# ICM-45686.net
KiCad netlist of a schematic drawn in EasyEDA Pro
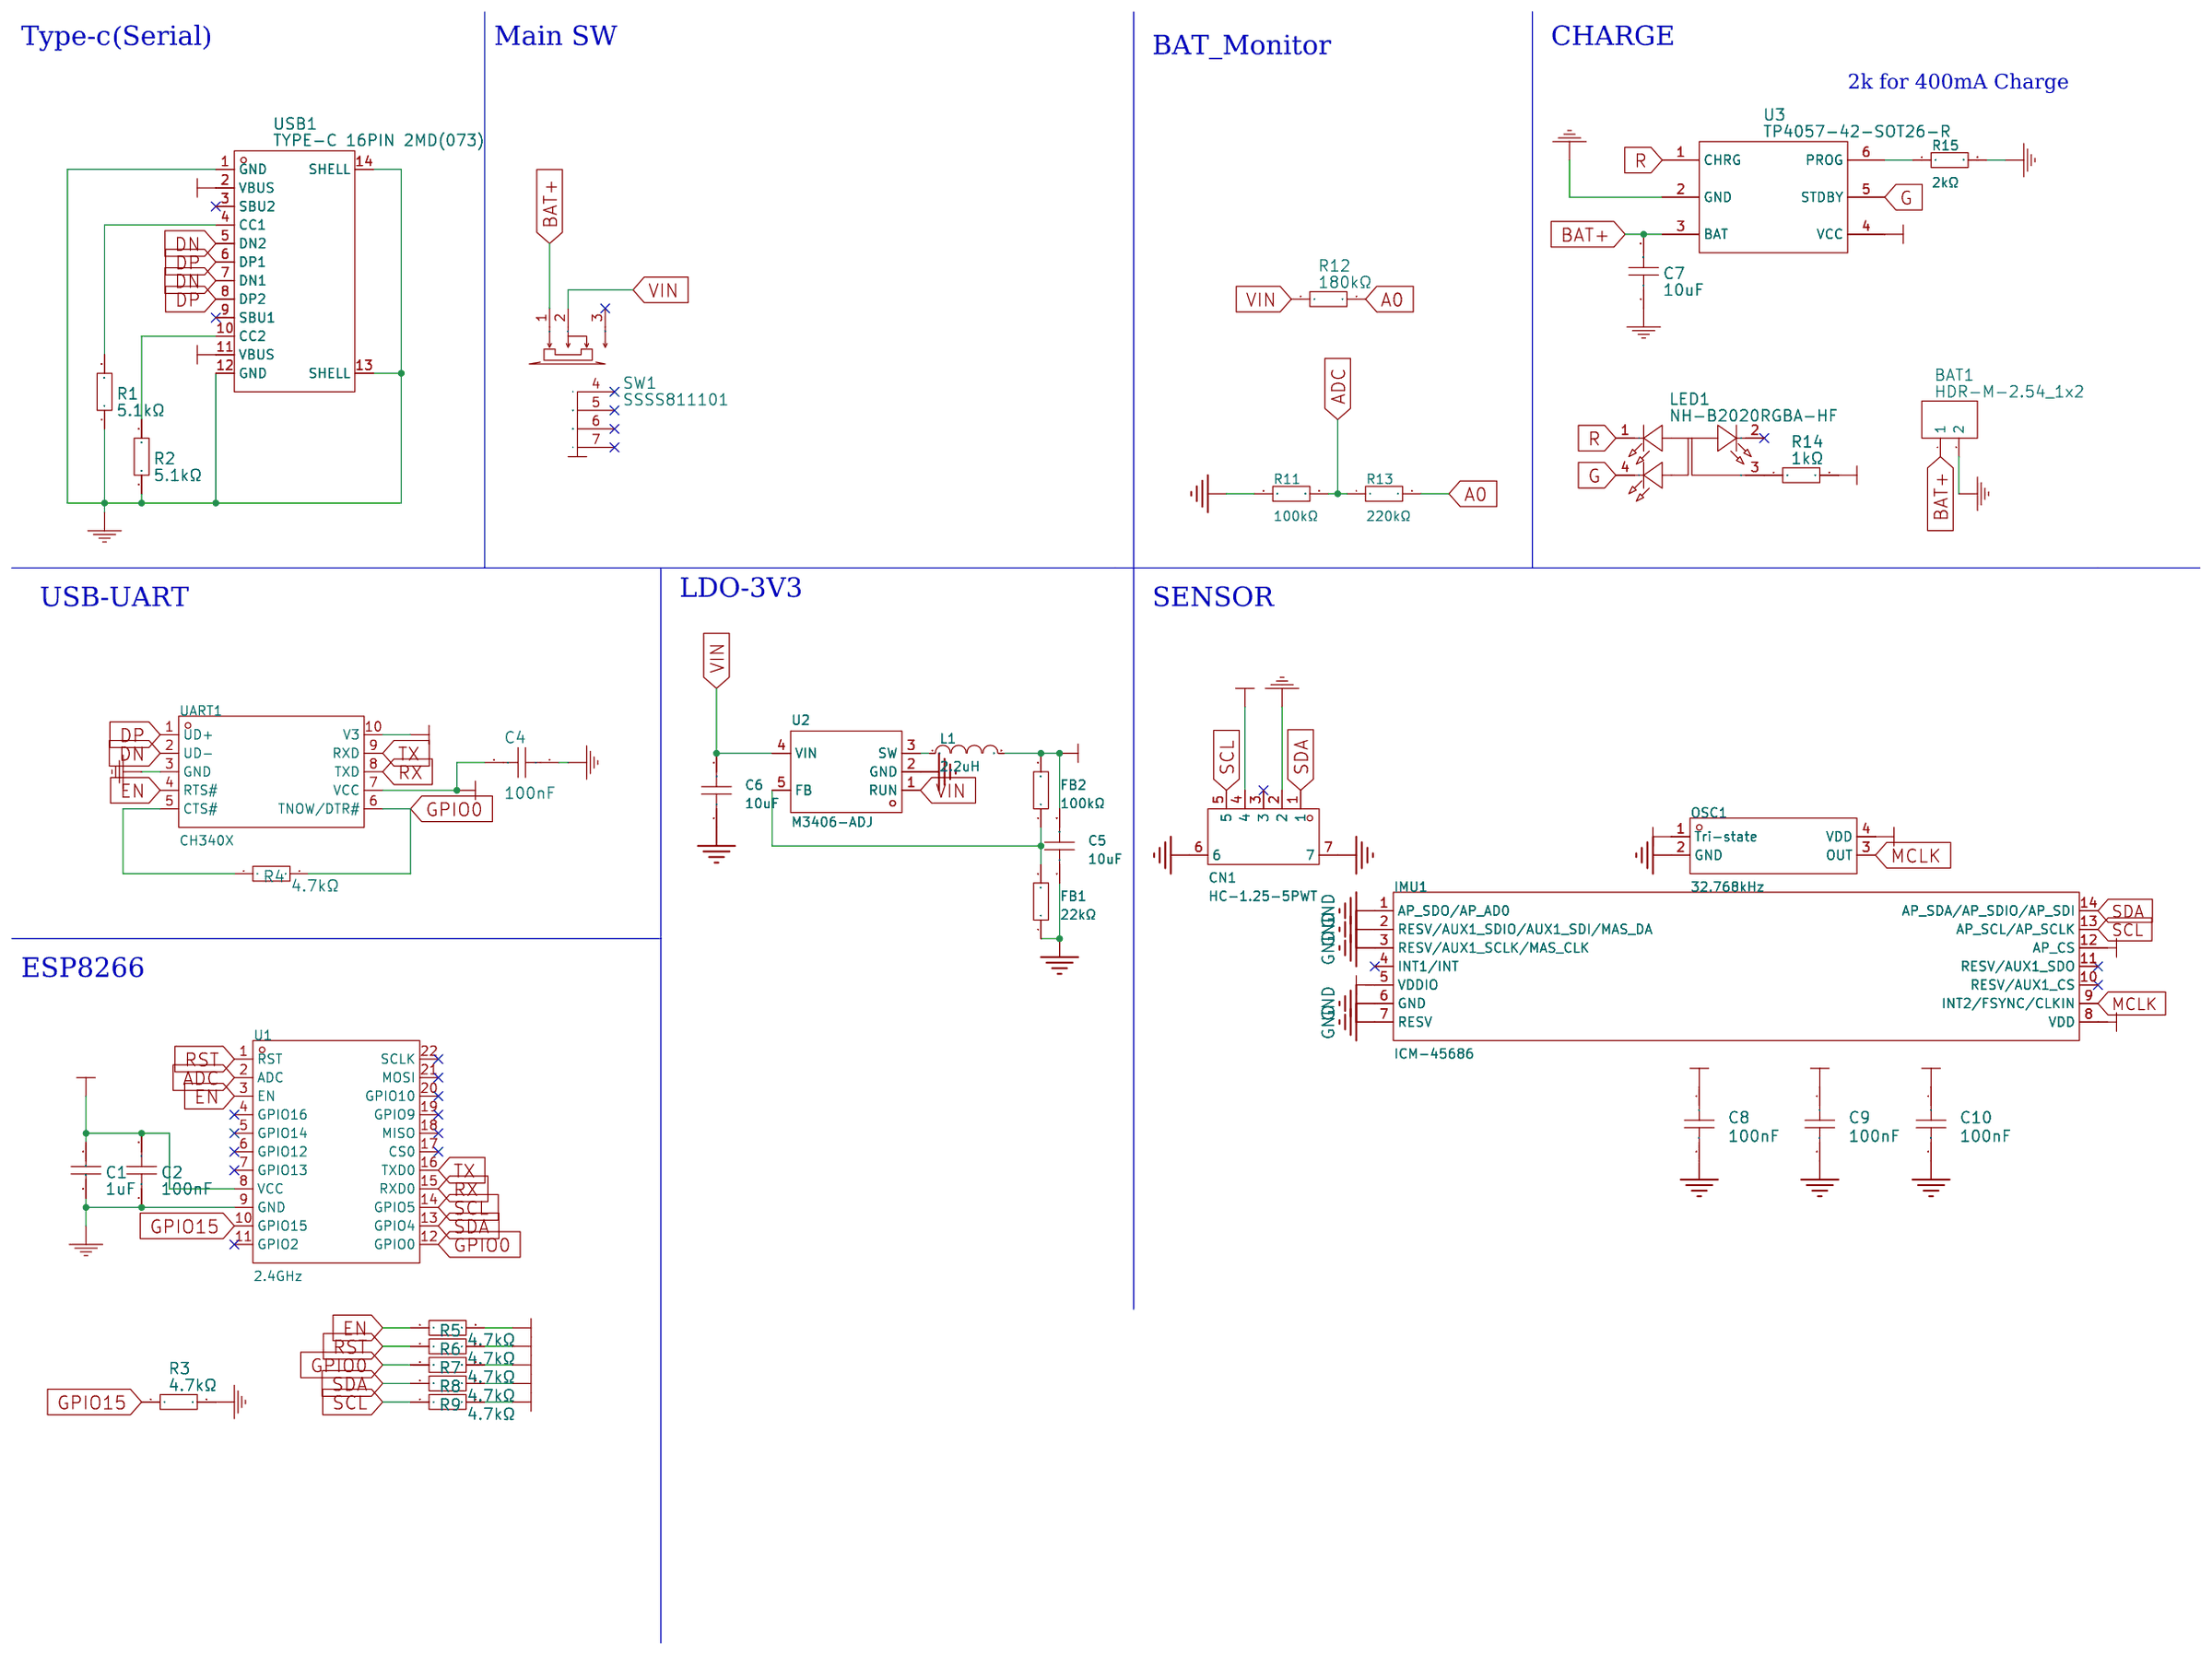
[diagram p0: schematic sheet]

(export (version "E")
  (design (tool "Eeschema 10.0.6"))
  (components
    (comp (ref "BAT1")
      (value "HDR-M-2.54_1x2")
      (footprint "easyedapro:HDR-M-2.54_1X2")
      (libsource (lib "easyedapro") (part "HDR-M-2.54_1x2"))
    )
    (comp (ref "C1")
      (value "1uF")
      (footprint "easyedapro:C0603")
      (fields
        (field (name "Manufacturer Part") "CL10A105KB8NNNC")
        (field (name "Manufacturer") "SAMSUNG(三星)")
      )
      (libsource (lib "easyedapro") (part "1uF"))
    )
    (comp (ref "C2")
      (value "100nF")
      (footprint "easyedapro:C0603")
      (fields
        (field (name "Manufacturer Part") "CC0603KRX7R9BB104")
        (field (name "Manufacturer") "YAGEO(国巨)")
      )
      (libsource (lib "easyedapro") (part "100nF"))
    )
    (comp (ref "C4")
      (value "100nF")
      (footprint "easyedapro:C0603")
      (fields
        (field (name "Manufacturer Part") "CC0603KRX7R9BB104")
        (field (name "Manufacturer") "YAGEO(国巨)")
      )
      (libsource (lib "easyedapro") (part "100nF"))
    )
    (comp (ref "C5")
      (value "10uF")
      (footprint "easyedapro:C0603")
      (description "容值:10uF;精度:±10%;额定电压:10V;材质(温度系数):X5R;")
      (fields
        (field (name "Manufacturer Part") "CL10A106KP8NNNC")
        (field (name "Manufacturer") "SAMSUNG(三星)")
      )
      (libsource (lib "easyedapro") (part "CL10A106KP8NNNC"))
    )
    (comp (ref "C6")
      (value "10uF")
      (footprint "easyedapro:C0603")
      (description "容值:10uF;精度:±10%;额定电压:10V;材质(温度系数):X5R;")
      (fields
        (field (name "Manufacturer Part") "CL10A106KP8NNNC")
        (field (name "Manufacturer") "SAMSUNG(三星)")
      )
      (libsource (lib "easyedapro") (part "CL10A106KP8NNNC"))
    )
    (comp (ref "C7")
      (value "10uF")
      (footprint "easyedapro:C0603")
      (fields
        (field (name "Manufacturer Part") "CL10A106KP8NNNC")
        (field (name "Manufacturer") "SAMSUNG(三星)")
      )
      (libsource (lib "easyedapro") (part "10uF"))
    )
    (comp (ref "C8")
      (value "100nF")
      (footprint "easyedapro:C0603")
      (fields
        (field (name "Manufacturer Part") "CC0603KRX7R9BB104")
        (field (name "Manufacturer") "YAGEO(国巨)")
      )
      (libsource (lib "easyedapro") (part "100nF"))
    )
    (comp (ref "C9")
      (value "100nF")
      (footprint "easyedapro:C0603")
      (fields
        (field (name "Manufacturer Part") "CC0603KRX7R9BB104")
        (field (name "Manufacturer") "YAGEO(国巨)")
      )
      (libsource (lib "easyedapro") (part "100nF"))
    )
    (comp (ref "C10")
      (value "100nF")
      (footprint "easyedapro:C0603")
      (fields
        (field (name "Manufacturer Part") "CC0603KRX7R9BB104")
        (field (name "Manufacturer") "YAGEO(国巨)")
      )
      (libsource (lib "easyedapro") (part "100nF"))
    )
    (comp (ref "CN1")
      (value "HC-1.25-5PWT")
      (footprint "easyedapro:CONN-SMD_5P-P1.25_HCTL_HC-1.25-5PWT")
      (description "参考系列:-;间距:1.25mm;插针结构:1x5P;排数:1;每排PIN数:5;行距:-;公母:公型插针;安装方式:卧贴;额定电流:1A;工作温度范围:-25°C~+85°C;")
      (fields (field (name "Manufacturer") "HCTL(华灿天禄)"))
      (libsource (lib "easyedapro") (part "HC-1.25-5PWT"))
    )
    (comp (ref "FB1")
      (value "22kΩ")
      (footprint "easyedapro:R0402")
      (description "电阻类型:厚膜电阻;阻值:22kΩ;精度:±1%;功率:62.5mW;")
      (fields
        (field (name "Manufacturer Part") "0402WGF2202TCE")
        (field (name "Manufacturer") "UNI-ROYAL(厚声)")
      )
      (libsource (lib "easyedapro") (part "0402WGF2202TCE"))
    )
    (comp (ref "FB2")
      (value "100kΩ")
      (footprint "easyedapro:R0402")
      (description "电阻类型:厚膜电阻;阻值:100kΩ;精度:±1%;功率:62.5mW;")
      (fields
        (field (name "Manufacturer Part") "0402WGF1003TCE")
        (field (name "Manufacturer") "UNI-ROYAL(厚声)")
      )
      (libsource (lib "easyedapro") (part "0402WGF1003TCE"))
    )
    (comp (ref "IMU1")
      (value "ICM-45686")
      (footprint "easyedapro:LGA-14_L3.0-W2.5-P0.50-TL")
      (fields (field (name "Manufacturer") "TDK InvenSense(应美盛)"))
      (libsource (lib "easyedapro") (part "ICM-45686"))
    )
    (comp (ref "L1")
      (value "2.2uH")
      (footprint "easyedapro:IND-SMD_L2.5-W2.0_YXMBL252010P")
      (description "类型:一体成型电感;电感值:2.2uH;精度:±20%;额定电流:2.1A;饱和电流(Isat):3A;")
      (fields (field (name "Manufacturer Part") "APH252010T2R2M") (field (name "Manufacturer") "APV(爱普微)"))
      (libsource (lib "easyedapro") (part "APH252010T2R2M"))
    )
    (comp (ref "LED1")
      (value "NH-B2020RGBA-HF")
      (footprint "easyedapro:LED-ARRAY-SMD_4P-L2.1-W2.1-TL_NH-B2020RGBA")
      (fields (field (name "Manufacturer") "国星光电"))
      (libsource (lib "easyedapro") (part "NH-B2020RGBA-HF"))
    )
    (comp (ref "OSC1")
      (value "32.768kHz")
      (footprint "easyedapro:OSC-SMD_4P-L3.2-W2.5-BL")
      (description "频率:32.768kHz;工作电压:1.8V~3.3V;")
      (fields
        (field (name "Manufacturer Part") "OK2EL89CJI-111YLC-32.768K")
        (field (name "Manufacturer") "YXC(扬兴晶振)")
      )
      (libsource (lib "easyedapro") (part "OK2EL89CJI-111YLC-32.768K"))
    )
    (comp (ref "R1")
      (value "5.1kΩ")
      (footprint "easyedapro:R0603")
      (fields
        (field (name "Manufacturer Part") "0603WAF5101T5E")
        (field (name "Manufacturer") "UNI-ROYAL(厚声)")
      )
      (libsource (lib "easyedapro") (part "5.1kΩ"))
    )
    (comp (ref "R2")
      (value "5.1kΩ")
      (footprint "easyedapro:R0603")
      (fields
        (field (name "Manufacturer Part") "0603WAF5101T5E")
        (field (name "Manufacturer") "UNI-ROYAL(厚声)")
      )
      (libsource (lib "easyedapro") (part "5.1kΩ"))
    )
    (comp (ref "R3")
      (value "4.7kΩ")
      (footprint "easyedapro:R0603")
      (fields
        (field (name "Manufacturer Part") "0603WAF4701T5E")
        (field (name "Manufacturer") "UNI-ROYAL(厚声)")
      )
      (libsource (lib "easyedapro") (part "4.7kΩ"))
    )
    (comp (ref "R4")
      (value "4.7kΩ")
      (footprint "easyedapro:R0603")
      (fields
        (field (name "Manufacturer Part") "0603WAF4701T5E")
        (field (name "Manufacturer") "UNI-ROYAL(厚声)")
      )
      (libsource (lib "easyedapro") (part "4.7kΩ"))
    )
    (comp (ref "R5")
      (value "4.7kΩ")
      (footprint "easyedapro:R0603")
      (fields
        (field (name "Manufacturer Part") "0603WAF4701T5E")
        (field (name "Manufacturer") "UNI-ROYAL(厚声)")
      )
      (libsource (lib "easyedapro") (part "4.7kΩ"))
    )
    (comp (ref "R6")
      (value "4.7kΩ")
      (footprint "easyedapro:R0603")
      (fields
        (field (name "Manufacturer Part") "0603WAF4701T5E")
        (field (name "Manufacturer") "UNI-ROYAL(厚声)")
      )
      (libsource (lib "easyedapro") (part "4.7kΩ"))
    )
    (comp (ref "R7")
      (value "4.7kΩ")
      (footprint "easyedapro:R0603")
      (fields
        (field (name "Manufacturer Part") "0603WAF4701T5E")
        (field (name "Manufacturer") "UNI-ROYAL(厚声)")
      )
      (libsource (lib "easyedapro") (part "4.7kΩ"))
    )
    (comp (ref "R8")
      (value "4.7kΩ")
      (footprint "easyedapro:R0603")
      (fields
        (field (name "Manufacturer Part") "0603WAF4701T5E")
        (field (name "Manufacturer") "UNI-ROYAL(厚声)")
      )
      (libsource (lib "easyedapro") (part "4.7kΩ"))
    )
    (comp (ref "R9")
      (value "4.7kΩ")
      (footprint "easyedapro:R0603")
      (fields
        (field (name "Manufacturer Part") "0603WAF4701T5E")
        (field (name "Manufacturer") "UNI-ROYAL(厚声)")
      )
      (libsource (lib "easyedapro") (part "4.7kΩ"))
    )
    (comp (ref "R11")
      (value "100kΩ")
      (footprint "easyedapro:R0603")
      (description "电阻类型:厚膜电阻;阻值:100kΩ;精度:±1%;功率:100mW;")
      (fields
        (field (name "Manufacturer Part") "0603WAF1003T5E")
        (field (name "Manufacturer") "UNI-ROYAL(厚声)")
      )
      (libsource (lib "easyedapro") (part "0603WAF1003T5E"))
    )
    (comp (ref "R12")
      (value "180kΩ")
      (footprint "easyedapro:R0603")
      (fields
        (field (name "Manufacturer Part") "0603WAF1803T5E")
        (field (name "Manufacturer") "UNI-ROYAL(厚声)")
      )
      (libsource (lib "easyedapro") (part "180kΩ"))
    )
    (comp (ref "R13")
      (value "220kΩ")
      (footprint "easyedapro:R0603")
      (description "电阻类型:厚膜电阻;阻值:220kΩ;精度:±1%;功率:100mW;")
      (fields
        (field (name "Manufacturer Part") "0603WAF2203T5E")
        (field (name "Manufacturer") "UNI-ROYAL(厚声)")
      )
      (libsource (lib "easyedapro") (part "0603WAF2203T5E"))
    )
    (comp (ref "R14")
      (value "1kΩ")
      (footprint "easyedapro:R0603")
      (fields
        (field (name "Manufacturer Part") "0603WAF1001T5E")
        (field (name "Manufacturer") "UNI-ROYAL(厚声)")
      )
      (libsource (lib "easyedapro") (part "1kΩ"))
    )
    (comp (ref "R15")
      (value "2kΩ")
      (footprint "easyedapro:R0603")
      (description "电阻类型:厚膜电阻;阻值:2kΩ;精度:±1%;功率:100mW;")
      (fields
        (field (name "Manufacturer Part") "0603WAF2001T5E")
        (field (name "Manufacturer") "UNI-ROYAL(厚声)")
      )
      (libsource (lib "easyedapro") (part "0603WAF2001T5E"))
    )
    (comp (ref "SW1")
      (value "SSSS811101")
      (footprint "easyedapro:SW-SMD_SSSS811101")
      (fields (field (name "Manufacturer") "ALPSALPINE(阿尔卑斯阿尔派)"))
      (libsource (lib "easyedapro") (part "SSSS811101"))
    )
    (comp (ref "U1")
      (value "2.4GHz")
      (footprint "easyedapro:WIFIM-SMD_ESP-12F-ESP8266MOD")
      (description "频率:2.4GHz;发射功率:16dBm;核心处理器:ESP8266;天线形式:PCB 板载天线;接收灵敏度:-90dBm;")
      (fields
        (field (name "Manufacturer Part") "ESP-12F(ESP8266MOD)")
        (field (name "Manufacturer") "Ai-Thinker(安信可)")
      )
      (libsource (lib "easyedapro") (part "ESP-12F(ESP8266MOD)"))
    )
    (comp (ref "U2")
      (value "M3406-ADJ")
      (footprint "easyedapro:SOT-23-5_L3.0-W1.7-P0.95-LS2.8-BR")
      (description "功能类型:降压型;同步整流:-;输出通道数:-;拓扑结构:-;输入电压:-;输出电流(最大值):-;开关频率:-;")
      (fields (field (name "Manufacturer") "西安航天民芯"))
      (libsource (lib "easyedapro") (part "M3406"))
    )
    (comp (ref "U3")
      (value "TP4057-42-SOT26-R")
      (footprint "easyedapro:SOT-23-6_L2.9-W1.6-P0.95-LS2.8-BL")
      (fields (field (name "Manufacturer") "TOPPOWER(南京拓微)"))
      (libsource (lib "easyedapro") (part "TP4057"))
    )
    (comp (ref "UART1")
      (value "CH340X")
      (footprint "easyedapro:MSOP-10_L3.0-W3.0-P0.50-LS5.0-BL")
      (fields (field (name "Manufacturer") "WCH(南京沁恒)"))
      (libsource (lib "easyedapro") (part "CH340X"))
    )
    (comp (ref "USB1")
      (value "TYPE-C 16PIN 2MD(073)")
      (footprint "easyedapro:USB-C-SMD_TYPE-C-6PIN-2MD-073")
      (fields (field (name "Manufacturer") "SHOU HAN(首韩)"))
      (libsource (lib "easyedapro") (part "TYPE-C 16PIN 2MD(073)"))
    )
  )
  (nets
    (net (code "1") (name "+5V") (class "Default")
      (node (ref "R14") (pin "2") (pinfunction "2_2") (pintype "input"))
      (node (ref "U3") (pin "4") (pinfunction "VCC_4") (pintype "unspecified"))
      (node (ref "USB1") (pin "11") (pinfunction "VBUS_11") (pintype "input"))
      (node (ref "USB1") (pin "2") (pinfunction "VBUS_2") (pintype "input"))
    )
    (net (code "2") (name "3V3") (class "Default")
      (node (ref "C1") (pin "2") (pinfunction "2_2") (pintype "input"))
      (node (ref "C10") (pin "1") (pinfunction "1_1") (pintype "input"))
      (node (ref "C2") (pin "2") (pinfunction "2_2") (pintype "input"))
      (node (ref "C4") (pin "2") (pinfunction "2_2") (pintype "input"))
      (node (ref "C5") (pin "2") (pinfunction "2_2") (pintype "unspecified"))
      (node (ref "C8") (pin "1") (pinfunction "1_1") (pintype "input"))
      (node (ref "C9") (pin "1") (pinfunction "1_1") (pintype "input"))
      (node (ref "CN1") (pin "4") (pinfunction "4_4") (pintype "unspecified"))
      (node (ref "FB2") (pin "2") (pinfunction "2_2") (pintype "input"))
      (node (ref "IMU1") (pin "12") (pinfunction "AP_CS_12") (pintype "unspecified"))
      (node (ref "IMU1") (pin "5") (pinfunction "VDDIO_5") (pintype "unspecified"))
      (node (ref "IMU1") (pin "8") (pinfunction "VDD_8") (pintype "unspecified"))
      (node (ref "L1") (pin "2") (pinfunction "2_2") (pintype "unspecified"))
      (node (ref "OSC1") (pin "1") (pinfunction "Tri-state_1") (pintype "unspecified"))
      (node (ref "OSC1") (pin "4") (pinfunction "VDD_4") (pintype "unspecified"))
      (node (ref "R5") (pin "2") (pinfunction "2_2") (pintype "input"))
      (node (ref "R6") (pin "2") (pinfunction "2_2") (pintype "input"))
      (node (ref "R7") (pin "2") (pinfunction "2_2") (pintype "input"))
      (node (ref "R8") (pin "2") (pinfunction "2_2") (pintype "input"))
      (node (ref "R9") (pin "2") (pinfunction "2_2") (pintype "input"))
      (node (ref "U1") (pin "8") (pinfunction "VCC_8") (pintype "input"))
      (node (ref "UART1") (pin "10") (pinfunction "V3_10") (pintype "unspecified"))
      (node (ref "UART1") (pin "7") (pinfunction "VCC_7") (pintype "unspecified"))
    )
    (net (code "3") (name "A0") (class "Default")
      (node (ref "R12") (pin "2") (pinfunction "2_2") (pintype "input"))
      (node (ref "R13") (pin "2") (pinfunction "2_2") (pintype "input"))
    )
    (net (code "4") (name "ADC") (class "Default")
      (node (ref "R11") (pin "2") (pinfunction "2_2") (pintype "input"))
      (node (ref "R13") (pin "1") (pinfunction "1_1") (pintype "input"))
      (node (ref "U1") (pin "2") (pinfunction "ADC_2") (pintype "input"))
    )
    (net (code "5") (name "BAT+") (class "Default")
      (node (ref "BAT1") (pin "1") (pinfunction "1_1") (pintype "input"))
      (node (ref "C7") (pin "2") (pinfunction "2_2") (pintype "input"))
      (node (ref "SW1") (pin "1") (pinfunction "1_1") (pintype "input"))
      (node (ref "U3") (pin "3") (pinfunction "BAT_3") (pintype "unspecified"))
    )
    (net (code "6") (name "DN") (class "Default")
      (node (ref "UART1") (pin "2") (pinfunction "UD-_2") (pintype "unspecified"))
      (node (ref "USB1") (pin "5") (pinfunction "DN2_5") (pintype "input"))
      (node (ref "USB1") (pin "7") (pinfunction "DN1_7") (pintype "input"))
    )
    (net (code "7") (name "DP") (class "Default")
      (node (ref "UART1") (pin "1") (pinfunction "UD+_1") (pintype "unspecified"))
      (node (ref "USB1") (pin "6") (pinfunction "DP1_6") (pintype "input"))
      (node (ref "USB1") (pin "8") (pinfunction "DP2_8") (pintype "input"))
    )
    (net (code "8") (name "EN") (class "Default")
      (node (ref "R5") (pin "1") (pinfunction "1_1") (pintype "input"))
      (node (ref "U1") (pin "3") (pinfunction "EN_3") (pintype "input"))
      (node (ref "UART1") (pin "4") (pinfunction "RTS#_4") (pintype "unspecified"))
    )
    (net (code "9") (name "G") (class "Default")
      (node (ref "LED1") (pin "4") (pinfunction "-_4") (pintype "input"))
      (node (ref "U3") (pin "5") (pinfunction "STDBY_5") (pintype "unspecified"))
    )
    (net (code "10") (name "GND") (class "Default")
      (node (ref "BAT1") (pin "2") (pinfunction "2_2") (pintype "input"))
      (node (ref "C1") (pin "1") (pinfunction "1_1") (pintype "input"))
      (node (ref "C10") (pin "2") (pinfunction "2_2") (pintype "input"))
      (node (ref "C2") (pin "1") (pinfunction "1_1") (pintype "input"))
      (node (ref "C4") (pin "1") (pinfunction "1_1") (pintype "input"))
      (node (ref "C5") (pin "1") (pinfunction "1_1") (pintype "unspecified"))
      (node (ref "C6") (pin "1") (pinfunction "1_1") (pintype "unspecified"))
      (node (ref "C7") (pin "1") (pinfunction "1_1") (pintype "input"))
      (node (ref "C8") (pin "2") (pinfunction "2_2") (pintype "input"))
      (node (ref "C9") (pin "2") (pinfunction "2_2") (pintype "input"))
      (node (ref "CN1") (pin "2") (pinfunction "2_2") (pintype "unspecified"))
      (node (ref "CN1") (pin "6") (pinfunction "6_6") (pintype "unspecified"))
      (node (ref "CN1") (pin "7") (pinfunction "7_7") (pintype "unspecified"))
      (node (ref "FB1") (pin "1") (pinfunction "1_1") (pintype "input"))
      (node (ref "IMU1") (pin "1") (pinfunction "AP_SDO/AP_AD0_1") (pintype "unspecified"))
      (node (ref "IMU1") (pin "2") (pinfunction "RESV/AUX1_SDIO/AUX1_SDI/MAS_DA_2") (pintype "unspecified"))
      (node (ref "IMU1") (pin "3") (pinfunction "RESV/AUX1_SCLK/MAS_CLK_3") (pintype "unspecified"))
      (node (ref "IMU1") (pin "6") (pinfunction "GND_6") (pintype "unspecified"))
      (node (ref "IMU1") (pin "7") (pinfunction "RESV_7") (pintype "unspecified"))
      (node (ref "OSC1") (pin "2") (pinfunction "GND_2") (pintype "unspecified"))
      (node (ref "R1") (pin "1") (pinfunction "1_1") (pintype "input"))
      (node (ref "R11") (pin "1") (pinfunction "1_1") (pintype "input"))
      (node (ref "R15") (pin "2") (pinfunction "2_2") (pintype "input"))
      (node (ref "R2") (pin "1") (pinfunction "1_1") (pintype "input"))
      (node (ref "R3") (pin "2") (pinfunction "2_2") (pintype "input"))
      (node (ref "U1") (pin "9") (pinfunction "GND_9") (pintype "input"))
      (node (ref "U2") (pin "2") (pinfunction "GND_2") (pintype "input"))
      (node (ref "U3") (pin "2") (pinfunction "GND_2") (pintype "unspecified"))
      (node (ref "UART1") (pin "3") (pinfunction "GND_3") (pintype "unspecified"))
      (node (ref "USB1") (pin "1") (pinfunction "GND_1") (pintype "input"))
      (node (ref "USB1") (pin "12") (pinfunction "GND_12") (pintype "input"))
      (node (ref "USB1") (pin "13") (pinfunction "SHELL_13") (pintype "input"))
      (node (ref "USB1") (pin "14") (pinfunction "SHELL_14") (pintype "input"))
    )
    (net (code "11") (name "GPIO0") (class "Default")
      (node (ref "R4") (pin "2") (pinfunction "2_2") (pintype "input"))
      (node (ref "R7") (pin "1") (pinfunction "1_1") (pintype "input"))
      (node (ref "U1") (pin "12") (pinfunction "GPIO0_12") (pintype "input"))
      (node (ref "UART1") (pin "6") (pinfunction "TNOW/DTR#_6") (pintype "unspecified"))
    )
    (net (code "12") (name "GPIO15") (class "Default")
      (node (ref "R3") (pin "1") (pinfunction "1_1") (pintype "input"))
      (node (ref "U1") (pin "10") (pinfunction "GPIO15_10") (pintype "input"))
    )
    (net (code "13") (name "MCLK") (class "Default")
      (node (ref "IMU1") (pin "9") (pinfunction "INT2/FSYNC/CLKIN_9") (pintype "unspecified"))
      (node (ref "OSC1") (pin "3") (pinfunction "OUT_3") (pintype "unspecified"))
    )
    (net (code "14") (name "Net-(LED1-+)") (class "Default")
      (node (ref "LED1") (pin "3") (pinfunction "+_3") (pintype "input"))
      (node (ref "R14") (pin "1") (pinfunction "1_1") (pintype "input"))
    )
    (net (code "15") (name "Net-(U2-FB)") (class "Default")
      (node (ref "FB1") (pin "2") (pinfunction "2_2") (pintype "input"))
      (node (ref "FB2") (pin "1") (pinfunction "1_1") (pintype "input"))
      (node (ref "U2") (pin "5") (pinfunction "FB_5") (pintype "input"))
    )
    (net (code "16") (name "Net-(U2-SW)") (class "Default")
      (node (ref "L1") (pin "1") (pinfunction "1_1") (pintype "unspecified"))
      (node (ref "U2") (pin "3") (pinfunction "SW_3") (pintype "input"))
    )
    (net (code "17") (name "Net-(U3-PROG)") (class "Default")
      (node (ref "R15") (pin "1") (pinfunction "1_1") (pintype "input"))
      (node (ref "U3") (pin "6") (pinfunction "PROG_6") (pintype "unspecified"))
    )
    (net (code "18") (name "Net-(UART1-CTS#)") (class "Default")
      (node (ref "R4") (pin "1") (pinfunction "1_1") (pintype "input"))
      (node (ref "UART1") (pin "5") (pinfunction "CTS#_5") (pintype "unspecified"))
    )
    (net (code "19") (name "Net-(USB1-CC1)") (class "Default")
      (node (ref "R1") (pin "2") (pinfunction "2_2") (pintype "input"))
      (node (ref "USB1") (pin "4") (pinfunction "CC1_4") (pintype "input"))
    )
    (net (code "20") (name "Net-(USB1-CC2)") (class "Default")
      (node (ref "R2") (pin "2") (pinfunction "2_2") (pintype "input"))
      (node (ref "USB1") (pin "10") (pinfunction "CC2_10") (pintype "input"))
    )
    (net (code "21") (name "R") (class "Default")
      (node (ref "LED1") (pin "1") (pinfunction "-_1") (pintype "input"))
      (node (ref "U3") (pin "1") (pinfunction "CHRG_1") (pintype "unspecified"))
    )
    (net (code "22") (name "RST") (class "Default")
      (node (ref "R6") (pin "1") (pinfunction "1_1") (pintype "input"))
      (node (ref "U1") (pin "1") (pinfunction "RST_1") (pintype "input"))
    )
    (net (code "23") (name "RX") (class "Default")
      (node (ref "U1") (pin "15") (pinfunction "RXD0_15") (pintype "input"))
      (node (ref "UART1") (pin "8") (pinfunction "TXD_8") (pintype "unspecified"))
    )
    (net (code "24") (name "SCL") (class "Default")
      (node (ref "CN1") (pin "5") (pinfunction "5_5") (pintype "unspecified"))
      (node (ref "IMU1") (pin "13") (pinfunction "AP_SCL/AP_SCLK_13") (pintype "unspecified"))
      (node (ref "R9") (pin "1") (pinfunction "1_1") (pintype "input"))
      (node (ref "U1") (pin "14") (pinfunction "GPIO5_14") (pintype "input"))
    )
    (net (code "25") (name "SDA") (class "Default")
      (node (ref "CN1") (pin "1") (pinfunction "1_1") (pintype "unspecified"))
      (node (ref "IMU1") (pin "14") (pinfunction "AP_SDA/AP_SDIO/AP_SDI_14") (pintype "unspecified"))
      (node (ref "R8") (pin "1") (pinfunction "1_1") (pintype "input"))
      (node (ref "U1") (pin "13") (pinfunction "GPIO4_13") (pintype "input"))
    )
    (net (code "26") (name "TX") (class "Default")
      (node (ref "U1") (pin "16") (pinfunction "TXD0_16") (pintype "input"))
      (node (ref "UART1") (pin "9") (pinfunction "RXD_9") (pintype "unspecified"))
    )
    (net (code "27") (name "VIN") (class "Default")
      (node (ref "C6") (pin "2") (pinfunction "2_2") (pintype "unspecified"))
      (node (ref "R12") (pin "1") (pinfunction "1_1") (pintype "input"))
      (node (ref "SW1") (pin "2") (pinfunction "2_2") (pintype "input"))
      (node (ref "U2") (pin "1") (pinfunction "RUN_1") (pintype "input"))
      (node (ref "U2") (pin "4") (pinfunction "VIN_4") (pintype "input"))
    )
    (net (code "28") (name "unconnected-(CN1-Pad3)") (class "Default")
      (node (ref "CN1") (pin "3") (pinfunction "3_3") (pintype "unspecified+no_connect"))
    )
    (net (code "29") (name "unconnected-(IMU1-INT1{slash}INT-Pad4)") (class "Default")
      (node (ref "IMU1") (pin "4") (pinfunction "INT1/INT_4") (pintype "unspecified+no_connect"))
    )
    (net (code "30") (name "unconnected-(IMU1-RESV{slash}AUX1_CS-Pad10)") (class "Default")
      (node (ref "IMU1") (pin "10") (pinfunction "RESV/AUX1_CS_10") (pintype "unspecified+no_connect"))
    )
    (net (code "31") (name "unconnected-(IMU1-RESV{slash}AUX1_SDO-Pad11)") (class "Default")
      (node (ref "IMU1") (pin "11") (pinfunction "RESV/AUX1_SDO_11") (pintype "unspecified+no_connect"))
    )
    (net (code "32") (name "unconnected-(LED1---Pad2)") (class "Default")
      (node (ref "LED1") (pin "2") (pinfunction "-_2") (pintype "input+no_connect"))
    )
    (net (code "33") (name "unconnected-(SW1-Pad3)") (class "Default")
      (node (ref "SW1") (pin "3") (pinfunction "3_3") (pintype "input+no_connect"))
    )
    (net (code "34") (name "unconnected-(SW1-Pad4)") (class "Default")
      (node (ref "SW1") (pin "4") (pinfunction "4_4") (pintype "input+no_connect"))
    )
    (net (code "35") (name "unconnected-(SW1-Pad5)") (class "Default")
      (node (ref "SW1") (pin "5") (pinfunction "5_5") (pintype "input+no_connect"))
    )
    (net (code "36") (name "unconnected-(SW1-Pad6)") (class "Default")
      (node (ref "SW1") (pin "6") (pinfunction "6_6") (pintype "input+no_connect"))
    )
    (net (code "37") (name "unconnected-(SW1-Pad7)") (class "Default")
      (node (ref "SW1") (pin "7") (pinfunction "7_7") (pintype "input+no_connect"))
    )
    (net (code "38") (name "unconnected-(U1-CS0-Pad17)") (class "Default")
      (node (ref "U1") (pin "17") (pinfunction "CS0_17") (pintype "input+no_connect"))
    )
    (net (code "39") (name "unconnected-(U1-GPIO2-Pad11)") (class "Default")
      (node (ref "U1") (pin "11") (pinfunction "GPIO2_11") (pintype "input+no_connect"))
    )
    (net (code "40") (name "unconnected-(U1-GPIO9-Pad19)") (class "Default")
      (node (ref "U1") (pin "19") (pinfunction "GPIO9_19") (pintype "input+no_connect"))
    )
    (net (code "41") (name "unconnected-(U1-GPIO10-Pad20)") (class "Default")
      (node (ref "U1") (pin "20") (pinfunction "GPIO10_20") (pintype "input+no_connect"))
    )
    (net (code "42") (name "unconnected-(U1-GPIO12-Pad6)") (class "Default")
      (node (ref "U1") (pin "6") (pinfunction "GPIO12_6") (pintype "input+no_connect"))
    )
    (net (code "43") (name "unconnected-(U1-GPIO13-Pad7)") (class "Default")
      (node (ref "U1") (pin "7") (pinfunction "GPIO13_7") (pintype "input+no_connect"))
    )
    (net (code "44") (name "unconnected-(U1-GPIO14-Pad5)") (class "Default")
      (node (ref "U1") (pin "5") (pinfunction "GPIO14_5") (pintype "input+no_connect"))
    )
    (net (code "45") (name "unconnected-(U1-GPIO16-Pad4)") (class "Default")
      (node (ref "U1") (pin "4") (pinfunction "GPIO16_4") (pintype "input+no_connect"))
    )
    (net (code "46") (name "unconnected-(U1-MISO-Pad18)") (class "Default")
      (node (ref "U1") (pin "18") (pinfunction "MISO_18") (pintype "input+no_connect"))
    )
    (net (code "47") (name "unconnected-(U1-MOSI-Pad21)") (class "Default")
      (node (ref "U1") (pin "21") (pinfunction "MOSI_21") (pintype "input+no_connect"))
    )
    (net (code "48") (name "unconnected-(U1-SCLK-Pad22)") (class "Default")
      (node (ref "U1") (pin "22") (pinfunction "SCLK_22") (pintype "input+no_connect"))
    )
    (net (code "49") (name "unconnected-(USB1-SBU1-Pad9)") (class "Default")
      (node (ref "USB1") (pin "9") (pinfunction "SBU1_9") (pintype "input+no_connect"))
    )
    (net (code "50") (name "unconnected-(USB1-SBU2-Pad3)") (class "Default")
      (node (ref "USB1") (pin "3") (pinfunction "SBU2_3") (pintype "input+no_connect"))
    )
  )
)
